# Esquematico_Wattimetro.net
KiCad netlist of a schematic drawn in Altium Designer
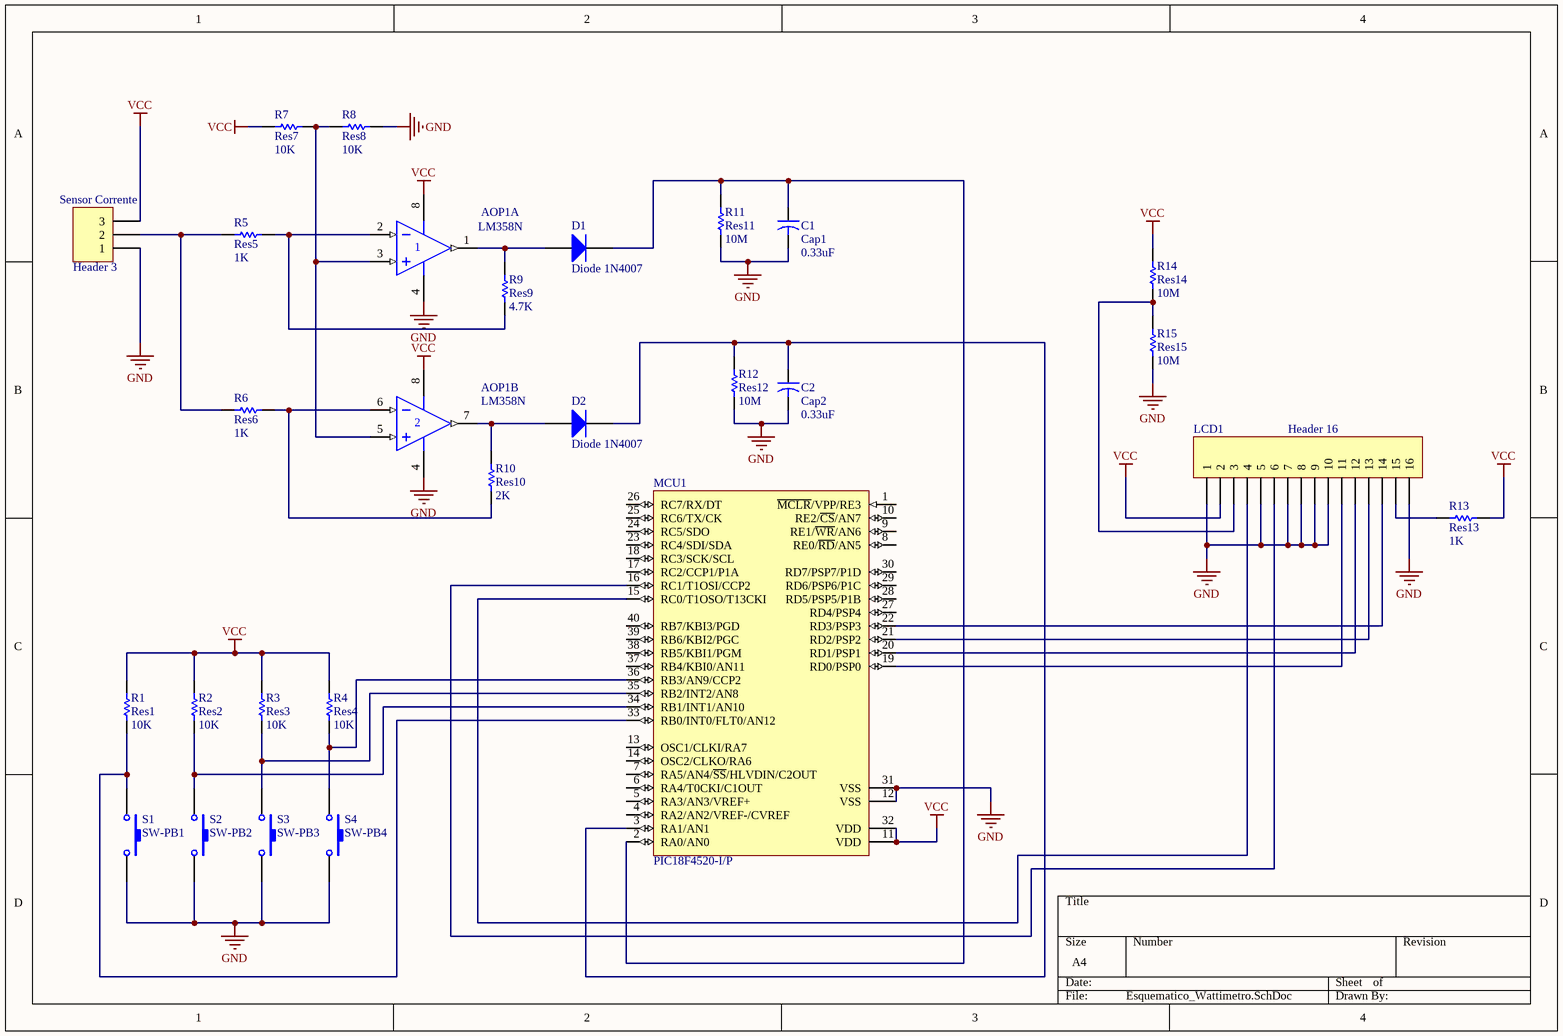
[diagram p0: Esquematico_Wattimetro.SchDoc]

(export (version "E")
  (design (tool "Eeschema 10.0.6"))
  (components
    (comp (ref "AOP1")
      (value "LM358N")
      (footprint "626-05")
      (description "Dual Low-Power Operational Amplifier")
      (fields (field (name "PUBLISHER") "Altium Limited"))
      (libsource (lib "Motorola Amplifier Operational Amplifier") (part "LM358N"))
    )
    (comp (ref "C1")
      (value "Cap1")
      (footprint "CAPR5-4X5")
      (description "Capacitor")
      (fields (field (name "ALTIUM_VALUE") "0.33uF") (field (name "PUBLISHER") "Altium Limited"))
      (libsource (lib "Miscellaneous Devices") (part "Cap2"))
    )
    (comp (ref "C2")
      (value "Cap2")
      (footprint "CAPR5-4X5")
      (description "Capacitor")
      (fields (field (name "ALTIUM_VALUE") "0.33uF") (field (name "PUBLISHER") "Altium Limited"))
      (libsource (lib "Miscellaneous Devices") (part "Cap2"))
    )
    (comp (ref "D1")
      (value "Diode 1N4007")
      (footprint "DO-41")
      (description "1 Amp General Purpose Rectifier")
      (fields (field (name "PUBLISHER") "Altium Limited"))
      (libsource (lib "Miscellaneous Devices") (part "Diode 1N4007"))
    )
    (comp (ref "D2")
      (value "Diode 1N4007")
      (footprint "DO-41")
      (description "1 Amp General Purpose Rectifier")
      (fields (field (name "PUBLISHER") "Altium Limited"))
      (libsource (lib "Miscellaneous Devices") (part "Diode 1N4007"))
    )
    (comp (ref "LCD1")
      (value "Header 16")
      (footprint "HDR1X16")
      (description "Header, 16-Pin")
      (fields (field (name "PUBLISHER") "Altium Limited"))
      (libsource (lib "Miscellaneous Connectors") (part "Header 16"))
    )
    (comp (ref "MCU1")
      (value "PIC18F4520-I/P")
      (footprint "PDIP600-P40")
      (fields (field (name "PUBLISHER") "Altium Limited"))
      (libsource (lib "Microchip Microcontroller 8-Bit PIC18") (part "PIC18F4520-I/P"))
    )
    (comp (ref "R1")
      (value "Res1")
      (footprint "AXIAL-0.3")
      (description "Resistor")
      (fields (field (name "ALTIUM_VALUE") "10K") (field (name "PUBLISHER") "Altium Limited"))
      (libsource (lib "Miscellaneous Devices") (part "Res1"))
    )
    (comp (ref "R2")
      (value "Res2")
      (footprint "AXIAL-0.3")
      (description "Resistor")
      (fields (field (name "ALTIUM_VALUE") "10K") (field (name "PUBLISHER") "Altium Limited"))
      (libsource (lib "Miscellaneous Devices") (part "Res1"))
    )
    (comp (ref "R3")
      (value "Res3")
      (footprint "AXIAL-0.3")
      (description "Resistor")
      (fields (field (name "ALTIUM_VALUE") "10K") (field (name "PUBLISHER") "Altium Limited"))
      (libsource (lib "Miscellaneous Devices") (part "Res1"))
    )
    (comp (ref "R4")
      (value "Res4")
      (footprint "AXIAL-0.3")
      (description "Resistor")
      (fields (field (name "ALTIUM_VALUE") "10K") (field (name "PUBLISHER") "Altium Limited"))
      (libsource (lib "Miscellaneous Devices") (part "Res1"))
    )
    (comp (ref "R5")
      (value "Res5")
      (footprint "AXIAL-0.3")
      (description "Resistor")
      (fields (field (name "ALTIUM_VALUE") "1K") (field (name "PUBLISHER") "Altium Limited"))
      (libsource (lib "Miscellaneous Devices") (part "Res1"))
    )
    (comp (ref "R6")
      (value "Res6")
      (footprint "AXIAL-0.3")
      (description "Resistor")
      (fields (field (name "ALTIUM_VALUE") "1K") (field (name "PUBLISHER") "Altium Limited"))
      (libsource (lib "Miscellaneous Devices") (part "Res1"))
    )
    (comp (ref "R7")
      (value "Res7")
      (footprint "AXIAL-0.3")
      (description "Resistor")
      (fields (field (name "ALTIUM_VALUE") "10K") (field (name "PUBLISHER") "Altium Limited"))
      (libsource (lib "Miscellaneous Devices") (part "Res1"))
    )
    (comp (ref "R8")
      (value "Res8")
      (footprint "AXIAL-0.3")
      (description "Resistor")
      (fields (field (name "ALTIUM_VALUE") "10K") (field (name "PUBLISHER") "Altium Limited"))
      (libsource (lib "Miscellaneous Devices") (part "Res1"))
    )
    (comp (ref "R9")
      (value "Res9")
      (footprint "AXIAL-0.3")
      (description "Resistor")
      (fields (field (name "ALTIUM_VALUE") "4.7K") (field (name "PUBLISHER") "Altium Limited"))
      (libsource (lib "Miscellaneous Devices") (part "Res1"))
    )
    (comp (ref "R10")
      (value "Res10")
      (footprint "AXIAL-0.3")
      (description "Resistor")
      (fields (field (name "ALTIUM_VALUE") "2K") (field (name "PUBLISHER") "Altium Limited"))
      (libsource (lib "Miscellaneous Devices") (part "Res1"))
    )
    (comp (ref "R11")
      (value "Res11")
      (footprint "AXIAL-0.3")
      (description "Resistor")
      (fields (field (name "ALTIUM_VALUE") "10M") (field (name "PUBLISHER") "Altium Limited"))
      (libsource (lib "Miscellaneous Devices") (part "Res1"))
    )
    (comp (ref "R12")
      (value "Res12")
      (footprint "AXIAL-0.3")
      (description "Resistor")
      (fields (field (name "ALTIUM_VALUE") "10M") (field (name "PUBLISHER") "Altium Limited"))
      (libsource (lib "Miscellaneous Devices") (part "Res1"))
    )
    (comp (ref "R13")
      (value "Res13")
      (footprint "AXIAL-0.3")
      (description "Resistor")
      (fields (field (name "ALTIUM_VALUE") "1K") (field (name "PUBLISHER") "Altium Limited"))
      (libsource (lib "Miscellaneous Devices") (part "Res1"))
    )
    (comp (ref "R14")
      (value "Res14")
      (footprint "AXIAL-0.3")
      (description "Resistor")
      (fields (field (name "ALTIUM_VALUE") "10M") (field (name "PUBLISHER") "Altium Limited"))
      (libsource (lib "Miscellaneous Devices") (part "Res1"))
    )
    (comp (ref "R15")
      (value "Res15")
      (footprint "AXIAL-0.3")
      (description "Resistor")
      (fields (field (name "ALTIUM_VALUE") "10M") (field (name "PUBLISHER") "Altium Limited"))
      (libsource (lib "Miscellaneous Devices") (part "Res1"))
    )
    (comp (ref "S1")
      (value "SW-PB1")
      (footprint "SPST-2")
      (description "Switch")
      (fields (field (name "PUBLISHER") "Altium Limited"))
      (libsource (lib "Miscellaneous Devices") (part "SW-PB"))
    )
    (comp (ref "S2")
      (value "SW-PB2")
      (footprint "SPST-2")
      (description "Switch")
      (fields (field (name "PUBLISHER") "Altium Limited"))
      (libsource (lib "Miscellaneous Devices") (part "SW-PB"))
    )
    (comp (ref "S3")
      (value "SW-PB3")
      (footprint "SPST-2")
      (description "Switch")
      (fields (field (name "PUBLISHER") "Altium Limited"))
      (libsource (lib "Miscellaneous Devices") (part "SW-PB"))
    )
    (comp (ref "S4")
      (value "SW-PB4")
      (footprint "SPST-2")
      (description "Switch")
      (fields (field (name "PUBLISHER") "Altium Limited"))
      (libsource (lib "Miscellaneous Devices") (part "SW-PB"))
    )
    (comp (ref "Sensor Corrente")
      (value "Header 3")
      (footprint "HDR1X3")
      (description "Header, 3-Pin")
      (fields (field (name "PUBLISHER") "Altium Limited"))
      (libsource (lib "Miscellaneous Connectors") (part "Header 3"))
    )
  )
  (nets
    (net (code "1") (name "GND") (class "Default")
      (node (ref "AOP1") (pin "4") (pinfunction "V-_4") (pintype "power_in"))
      (node (ref "C1") (pin "2") (pinfunction "2_2") (pintype "passive"))
      (node (ref "C2") (pin "2") (pinfunction "2_2") (pintype "passive"))
      (node (ref "LCD1") (pin "1") (pinfunction "1_1") (pintype "passive"))
      (node (ref "LCD1") (pin "10") (pinfunction "10_10") (pintype "passive"))
      (node (ref "LCD1") (pin "16") (pinfunction "16_16") (pintype "passive"))
      (node (ref "LCD1") (pin "5") (pinfunction "5_5") (pintype "passive"))
      (node (ref "LCD1") (pin "7") (pinfunction "7_7") (pintype "passive"))
      (node (ref "LCD1") (pin "8") (pinfunction "8_8") (pintype "passive"))
      (node (ref "LCD1") (pin "9") (pinfunction "9_9") (pintype "passive"))
      (node (ref "MCU1") (pin "12") (pinfunction "VSS_12") (pintype "power_in"))
      (node (ref "MCU1") (pin "31") (pinfunction "VSS_31") (pintype "power_in"))
      (node (ref "R11") (pin "1") (pinfunction "1_1") (pintype "passive"))
      (node (ref "R12") (pin "1") (pinfunction "1_1") (pintype "passive"))
      (node (ref "R15") (pin "1") (pinfunction "1_1") (pintype "passive"))
      (node (ref "R8") (pin "1") (pinfunction "1_1") (pintype "passive"))
      (node (ref "S1") (pin "2") (pinfunction "2_2") (pintype "passive"))
      (node (ref "S2") (pin "2") (pinfunction "2_2") (pintype "passive"))
      (node (ref "S3") (pin "2") (pinfunction "2_2") (pintype "passive"))
      (node (ref "S4") (pin "2") (pinfunction "2_2") (pintype "passive"))
      (node (ref "Sensor Corrente") (pin "1") (pinfunction "1_1") (pintype "passive"))
    )
    (net (code "2") (name "Net-(AOP1A-IN+)") (class "Default")
      (node (ref "AOP1") (pin "3") (pinfunction "IN+_3") (pintype "input"))
      (node (ref "AOP1") (pin "5") (pinfunction "IN+_5") (pintype "input"))
      (node (ref "R7") (pin "1") (pinfunction "1_1") (pintype "passive"))
      (node (ref "R8") (pin "2") (pinfunction "2_2") (pintype "passive"))
    )
    (net (code "3") (name "Net-(AOP1A-IN-)") (class "Default")
      (node (ref "AOP1") (pin "2") (pinfunction "IN-_2") (pintype "input"))
      (node (ref "R5") (pin "2") (pinfunction "2_2") (pintype "passive"))
      (node (ref "R9") (pin "1") (pinfunction "1_1") (pintype "passive"))
    )
    (net (code "4") (name "Net-(AOP1A-OUT)") (class "Default")
      (node (ref "AOP1") (pin "1") (pinfunction "OUT_1") (pintype "output"))
      (node (ref "D1") (pin "1") (pinfunction "A_1") (pintype "passive"))
      (node (ref "R9") (pin "2") (pinfunction "2_2") (pintype "passive"))
    )
    (net (code "5") (name "Net-(AOP1B-IN-)") (class "Default")
      (node (ref "AOP1") (pin "6") (pinfunction "IN-_6") (pintype "input"))
      (node (ref "R10") (pin "2") (pinfunction "2_2") (pintype "passive"))
      (node (ref "R6") (pin "2") (pinfunction "2_2") (pintype "passive"))
    )
    (net (code "6") (name "Net-(AOP1B-OUT)") (class "Default")
      (node (ref "AOP1") (pin "7") (pinfunction "OUT_7") (pintype "output"))
      (node (ref "D2") (pin "1") (pinfunction "A_1") (pintype "passive"))
      (node (ref "R10") (pin "1") (pinfunction "1_1") (pintype "passive"))
    )
    (net (code "7") (name "Net-(D1-K)") (class "Default")
      (node (ref "C1") (pin "1") (pinfunction "1_1") (pintype "passive"))
      (node (ref "D1") (pin "2") (pinfunction "K_2") (pintype "passive"))
      (node (ref "MCU1") (pin "2") (pinfunction "RA0/AN0_2") (pintype "bidirectional"))
      (node (ref "R11") (pin "2") (pinfunction "2_2") (pintype "passive"))
    )
    (net (code "8") (name "Net-(D2-K)") (class "Default")
      (node (ref "C2") (pin "1") (pinfunction "1_1") (pintype "passive"))
      (node (ref "D2") (pin "2") (pinfunction "K_2") (pintype "passive"))
      (node (ref "MCU1") (pin "3") (pinfunction "RA1/AN1_3") (pintype "bidirectional"))
      (node (ref "R12") (pin "2") (pinfunction "2_2") (pintype "passive"))
    )
    (net (code "9") (name "Net-(LCD1-Pad3)") (class "Default")
      (node (ref "LCD1") (pin "3") (pinfunction "3_3") (pintype "passive"))
      (node (ref "R14") (pin "1") (pinfunction "1_1") (pintype "passive"))
      (node (ref "R15") (pin "2") (pinfunction "2_2") (pintype "passive"))
    )
    (net (code "10") (name "Net-(LCD1-Pad15)") (class "Default")
      (node (ref "LCD1") (pin "15") (pinfunction "15_15") (pintype "passive"))
      (node (ref "R13") (pin "2") (pinfunction "2_2") (pintype "passive"))
    )
    (net (code "11") (name "Net-(MCU1-RB0{slash}INT0{slash}FLT0{slash}AN12)") (class "Default")
      (node (ref "MCU1") (pin "33") (pinfunction "RB0/INT0/FLT0/AN12_33") (pintype "bidirectional"))
      (node (ref "R1") (pin "1") (pinfunction "1_1") (pintype "passive"))
      (node (ref "S1") (pin "1") (pinfunction "1_1") (pintype "passive"))
    )
    (net (code "12") (name "Net-(MCU1-RB1{slash}INT1{slash}AN10)") (class "Default")
      (node (ref "MCU1") (pin "34") (pinfunction "RB1/INT1/AN10_34") (pintype "bidirectional"))
      (node (ref "R2") (pin "1") (pinfunction "1_1") (pintype "passive"))
      (node (ref "S2") (pin "1") (pinfunction "1_1") (pintype "passive"))
    )
    (net (code "13") (name "Net-(MCU1-RB2{slash}INT2{slash}AN8)") (class "Default")
      (node (ref "MCU1") (pin "35") (pinfunction "RB2/INT2/AN8_35") (pintype "bidirectional"))
      (node (ref "R3") (pin "1") (pinfunction "1_1") (pintype "passive"))
      (node (ref "S3") (pin "1") (pinfunction "1_1") (pintype "passive"))
    )
    (net (code "14") (name "Net-(MCU1-RB3{slash}AN9{slash}CCP2)") (class "Default")
      (node (ref "MCU1") (pin "36") (pinfunction "RB3/AN9/CCP2_36") (pintype "bidirectional"))
      (node (ref "R4") (pin "1") (pinfunction "1_1") (pintype "passive"))
      (node (ref "S4") (pin "1") (pinfunction "1_1") (pintype "passive"))
    )
    (net (code "15") (name "Net-(MCU1-RC0{slash}T1OSO{slash}T13CKI)") (class "Default")
      (node (ref "LCD1") (pin "4") (pinfunction "4_4") (pintype "passive"))
      (node (ref "MCU1") (pin "15") (pinfunction "RC0/T1OSO/T13CKI_15") (pintype "bidirectional"))
    )
    (net (code "16") (name "Net-(MCU1-RC1{slash}T1OSI{slash}CCP2)") (class "Default")
      (node (ref "LCD1") (pin "6") (pinfunction "6_6") (pintype "passive"))
      (node (ref "MCU1") (pin "16") (pinfunction "RC1/T1OSI/CCP2_16") (pintype "bidirectional"))
    )
    (net (code "17") (name "Net-(MCU1-RD0{slash}PSP0)") (class "Default")
      (node (ref "LCD1") (pin "11") (pinfunction "11_11") (pintype "passive"))
      (node (ref "MCU1") (pin "19") (pinfunction "RD0/PSP0_19") (pintype "bidirectional"))
    )
    (net (code "18") (name "Net-(MCU1-RD1{slash}PSP1)") (class "Default")
      (node (ref "LCD1") (pin "12") (pinfunction "12_12") (pintype "passive"))
      (node (ref "MCU1") (pin "20") (pinfunction "RD1/PSP1_20") (pintype "bidirectional"))
    )
    (net (code "19") (name "Net-(MCU1-RD2{slash}PSP2)") (class "Default")
      (node (ref "LCD1") (pin "13") (pinfunction "13_13") (pintype "passive"))
      (node (ref "MCU1") (pin "21") (pinfunction "RD2/PSP2_21") (pintype "bidirectional"))
    )
    (net (code "20") (name "Net-(MCU1-RD3{slash}PSP3)") (class "Default")
      (node (ref "LCD1") (pin "14") (pinfunction "14_14") (pintype "passive"))
      (node (ref "MCU1") (pin "22") (pinfunction "RD3/PSP3_22") (pintype "bidirectional"))
    )
    (net (code "21") (name "Net-(R5-Pad1)") (class "Default")
      (node (ref "R5") (pin "1") (pinfunction "1_1") (pintype "passive"))
      (node (ref "R6") (pin "1") (pinfunction "1_1") (pintype "passive"))
      (node (ref "Sensor Corrente") (pin "2") (pinfunction "2_2") (pintype "passive"))
    )
    (net (code "22") (name "VCC") (class "Default")
      (node (ref "AOP1") (pin "8") (pinfunction "V+_8") (pintype "power_in"))
      (node (ref "LCD1") (pin "2") (pinfunction "2_2") (pintype "passive"))
      (node (ref "MCU1") (pin "11") (pinfunction "VDD_11") (pintype "power_in"))
      (node (ref "MCU1") (pin "32") (pinfunction "VDD_32") (pintype "power_in"))
      (node (ref "R1") (pin "2") (pinfunction "2_2") (pintype "passive"))
      (node (ref "R13") (pin "1") (pinfunction "1_1") (pintype "passive"))
      (node (ref "R14") (pin "2") (pinfunction "2_2") (pintype "passive"))
      (node (ref "R2") (pin "2") (pinfunction "2_2") (pintype "passive"))
      (node (ref "R3") (pin "2") (pinfunction "2_2") (pintype "passive"))
      (node (ref "R4") (pin "2") (pinfunction "2_2") (pintype "passive"))
      (node (ref "R7") (pin "2") (pinfunction "2_2") (pintype "passive"))
      (node (ref "Sensor Corrente") (pin "3") (pinfunction "3_3") (pintype "passive"))
    )
    (net (code "23") (name "unconnected-(MCU1-OSC1{slash}CLKI{slash}RA7-Pad13)") (class "Default")
      (node (ref "MCU1") (pin "13") (pinfunction "OSC1/CLKI/RA7_13") (pintype "bidirectional"))
    )
    (net (code "24") (name "unconnected-(MCU1-OSC2{slash}CLKO{slash}RA6-Pad14)") (class "Default")
      (node (ref "MCU1") (pin "14") (pinfunction "OSC2/CLKO/RA6_14") (pintype "bidirectional"))
    )
    (net (code "25") (name "unconnected-(MCU1-RA2{slash}AN2{slash}VREF-{slash}CVREF-Pad4)") (class "Default")
      (node (ref "MCU1") (pin "4") (pinfunction "RA2/AN2/VREF-/CVREF_4") (pintype "bidirectional"))
    )
    (net (code "26") (name "unconnected-(MCU1-RA3{slash}AN3{slash}VREF+-Pad5)") (class "Default")
      (node (ref "MCU1") (pin "5") (pinfunction "RA3/AN3/VREF+_5") (pintype "bidirectional"))
    )
    (net (code "27") (name "unconnected-(MCU1-RA4{slash}T0CKI{slash}C1OUT-Pad6)") (class "Default")
      (node (ref "MCU1") (pin "6") (pinfunction "RA4/T0CKI/C1OUT_6") (pintype "bidirectional"))
    )
    (net (code "28") (name "unconnected-(MCU1-RA5{slash}AN4{slash}~{SS}{slash}HLVDIN{slash}C2OUT-Pad7)") (class "Default")
      (node (ref "MCU1") (pin "7") (pinfunction "RA5/AN4/~{SS}/HLVDIN/C2OUT_7") (pintype "bidirectional"))
    )
    (net (code "29") (name "unconnected-(MCU1-RB4{slash}KBI0{slash}AN11-Pad37)") (class "Default")
      (node (ref "MCU1") (pin "37") (pinfunction "RB4/KBI0/AN11_37") (pintype "bidirectional"))
    )
    (net (code "30") (name "unconnected-(MCU1-RB5{slash}KBI1{slash}PGM-Pad38)") (class "Default")
      (node (ref "MCU1") (pin "38") (pinfunction "RB5/KBI1/PGM_38") (pintype "bidirectional"))
    )
    (net (code "31") (name "unconnected-(MCU1-RB6{slash}KBI2{slash}PGC-Pad39)") (class "Default")
      (node (ref "MCU1") (pin "39") (pinfunction "RB6/KBI2/PGC_39") (pintype "bidirectional"))
    )
    (net (code "32") (name "unconnected-(MCU1-RB7{slash}KBI3{slash}PGD-Pad40)") (class "Default")
      (node (ref "MCU1") (pin "40") (pinfunction "RB7/KBI3/PGD_40") (pintype "bidirectional"))
    )
    (net (code "33") (name "unconnected-(MCU1-RC2{slash}CCP1{slash}P1A-Pad17)") (class "Default")
      (node (ref "MCU1") (pin "17") (pinfunction "RC2/CCP1/P1A_17") (pintype "bidirectional"))
    )
    (net (code "34") (name "unconnected-(MCU1-RC3{slash}SCK{slash}SCL-Pad18)") (class "Default")
      (node (ref "MCU1") (pin "18") (pinfunction "RC3/SCK/SCL_18") (pintype "bidirectional"))
    )
    (net (code "35") (name "unconnected-(MCU1-RC4{slash}SDI{slash}SDA-Pad23)") (class "Default")
      (node (ref "MCU1") (pin "23") (pinfunction "RC4/SDI/SDA_23") (pintype "bidirectional"))
    )
    (net (code "36") (name "unconnected-(MCU1-RC5{slash}SDO-Pad24)") (class "Default")
      (node (ref "MCU1") (pin "24") (pinfunction "RC5/SDO_24") (pintype "bidirectional"))
    )
    (net (code "37") (name "unconnected-(MCU1-RC6{slash}TX{slash}CK-Pad25)") (class "Default")
      (node (ref "MCU1") (pin "25") (pinfunction "RC6/TX/CK_25") (pintype "bidirectional"))
    )
    (net (code "38") (name "unconnected-(MCU1-RC7{slash}RX{slash}DT-Pad26)") (class "Default")
      (node (ref "MCU1") (pin "26") (pinfunction "RC7/RX/DT_26") (pintype "bidirectional"))
    )
    (net (code "39") (name "unconnected-(MCU1-RD4{slash}PSP4-Pad27)") (class "Default")
      (node (ref "MCU1") (pin "27") (pinfunction "RD4/PSP4_27") (pintype "bidirectional"))
    )
    (net (code "40") (name "unconnected-(MCU1-RD5{slash}PSP5{slash}P1B-Pad28)") (class "Default")
      (node (ref "MCU1") (pin "28") (pinfunction "RD5/PSP5/P1B_28") (pintype "bidirectional"))
    )
    (net (code "41") (name "unconnected-(MCU1-RD6{slash}PSP6{slash}P1C-Pad29)") (class "Default")
      (node (ref "MCU1") (pin "29") (pinfunction "RD6/PSP6/P1C_29") (pintype "bidirectional"))
    )
    (net (code "42") (name "unconnected-(MCU1-RD7{slash}PSP7{slash}P1D-Pad30)") (class "Default")
      (node (ref "MCU1") (pin "30") (pinfunction "RD7/PSP7/P1D_30") (pintype "bidirectional"))
    )
    (net (code "43") (name "unconnected-(MCU1-RE0{slash}~{RD}{slash}AN5-Pad8)") (class "Default")
      (node (ref "MCU1") (pin "8") (pinfunction "RE0/~{RD}/AN5_8") (pintype "bidirectional"))
    )
    (net (code "44") (name "unconnected-(MCU1-RE1{slash}~{WR}{slash}AN6-Pad9)") (class "Default")
      (node (ref "MCU1") (pin "9") (pinfunction "RE1/~{WR}/AN6_9") (pintype "bidirectional"))
    )
    (net (code "45") (name "unconnected-(MCU1-RE2{slash}~{CS}{slash}AN7-Pad10)") (class "Default")
      (node (ref "MCU1") (pin "10") (pinfunction "RE2/~{CS}/AN7_10") (pintype "bidirectional"))
    )
    (net (code "46") (name "unconnected-(MCU1-~{MCLR}{slash}VPP{slash}RE3-Pad1)") (class "Default")
      (node (ref "MCU1") (pin "1") (pinfunction "~{MCLR}/VPP/RE3_1") (pintype "input"))
    )
  )
)
